# 5V_Regulator.net
KiCad netlist of a schematic drawn in Altium Designer
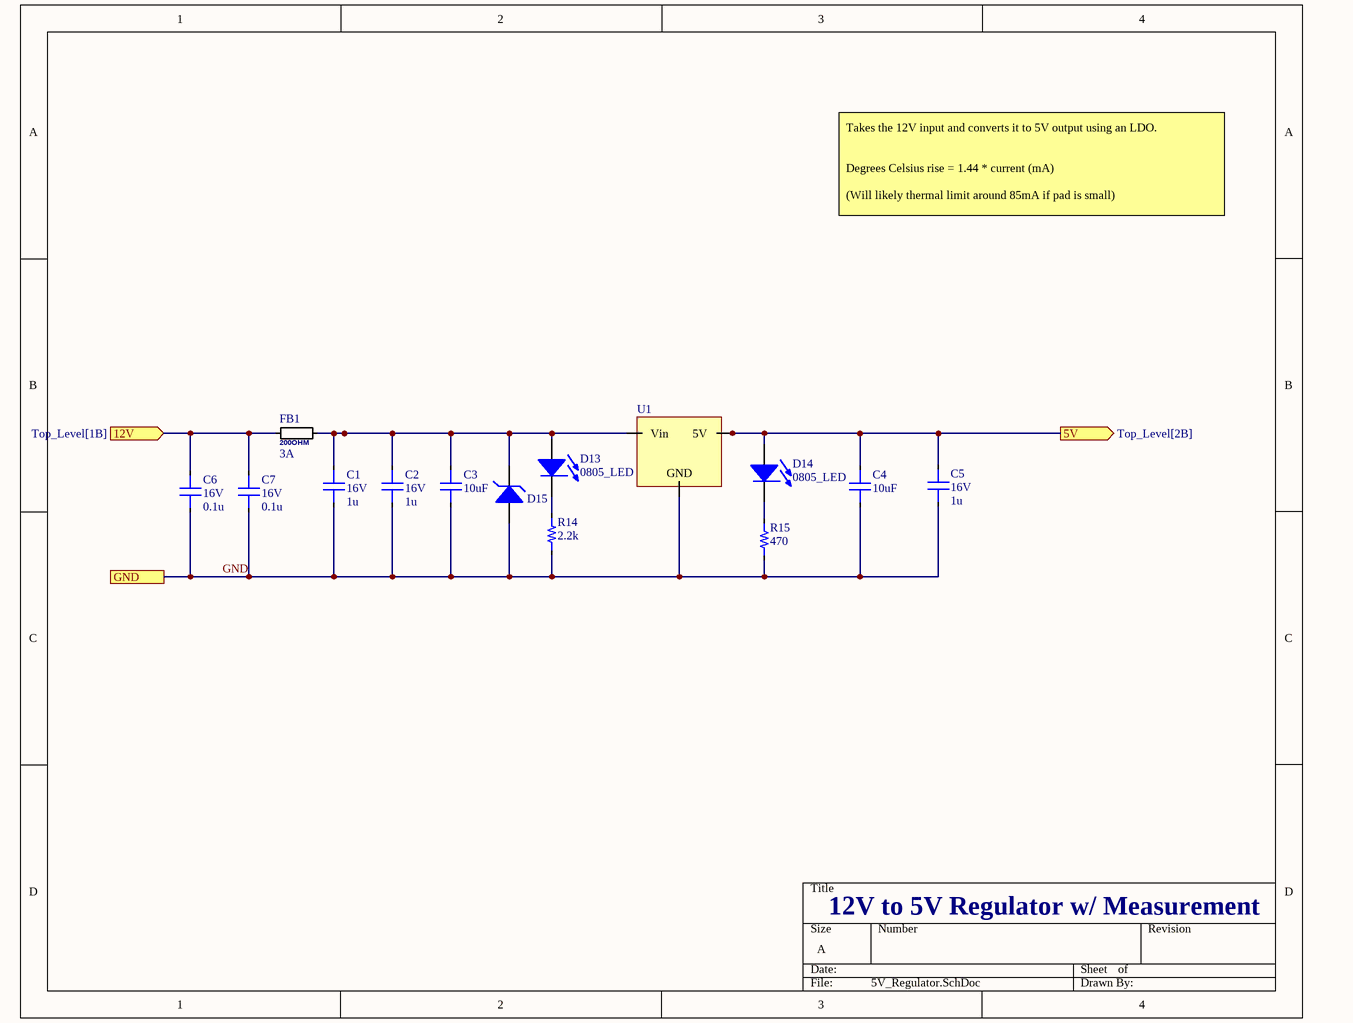
[diagram p0: 5V_Regulator.SchDoc]

(export (version "E")
  (design (tool "Eeschema 10.0.6"))
  (components
    (comp (ref "C1")
      (value "1u")
      (footprint "0603_CAP")
      (fields (field (name "VOLTAGE") "16V") (field (name "Comment") "Capacitor"))
      (libsource (lib "Capacitors") (part "Capacitor"))
    )
    (comp (ref "C2")
      (value "1u")
      (footprint "0603_CAP")
      (fields (field (name "VOLTAGE") "16V") (field (name "Comment") "Capacitor"))
      (libsource (lib "Capacitors") (part "Capacitor"))
    )
    (comp (ref "C3")
      (value "10uF")
      (footprint "0603_CAP")
      (fields (field (name "Comment") "Capacitor"))
      (libsource (lib "Capacitors") (part "Capacitor"))
    )
    (comp (ref "C4")
      (value "10uF")
      (footprint "0603_CAP")
      (fields (field (name "Comment") "Capacitor"))
      (libsource (lib "Capacitors") (part "Capacitor"))
    )
    (comp (ref "C5")
      (value "1u")
      (footprint "0603_CAP")
      (fields (field (name "VOLTAGE") "16V") (field (name "Comment") "Capacitor"))
      (libsource (lib "Capacitors") (part "Capacitor"))
    )
    (comp (ref "C6")
      (value "0.1u")
      (footprint "0603_CAP")
      (fields (field (name "VOLTAGE") "16V") (field (name "Comment") "Capacitor"))
      (libsource (lib "Capacitors") (part "Capacitor"))
    )
    (comp (ref "C7")
      (value "0.1u")
      (footprint "0603_CAP")
      (fields (field (name "VOLTAGE") "16V") (field (name "Comment") "Capacitor"))
      (libsource (lib "Capacitors") (part "Capacitor"))
    )
    (comp (ref "D13")
      (value "0805_LED")
      (footprint "0805_LED")
      (description "Generic 0805 LED")
      (libsource (lib "Diodes") (part "0805_LED"))
    )
    (comp (ref "D14")
      (value "0805_LED")
      (footprint "0805_LED")
      (description "Generic 0805 LED")
      (libsource (lib "Diodes") (part "0805_LED"))
    )
    (comp (ref "D15")
      (value "DDZ9701")
      (footprint "SOD-123")
      (description "Zener Diode 14V 500mW ±5% Surface Mount SOD-1")
      (libsource (lib "Diodes") (part "DDZ9701"))
    )
    (comp (ref "FB1")
      (value "*")
      (footprint "0805_Ferrite")
      (fields (field (name "=Z@100MHZ") "200OHM") (field (name "IMAX") "3A"))
      (libsource (lib "Magnetic") (part "ChipFerrite"))
    )
    (comp (ref "R14")
      (value "2.2k")
      (footprint "0603_RES")
      (fields (field (name "Comment") "Resistor"))
      (libsource (lib "Resistors") (part "Resistor"))
    )
    (comp (ref "R15")
      (value "470")
      (footprint "0603_RES")
      (fields (field (name "Comment") "Resistor"))
      (libsource (lib "Resistors") (part "Resistor"))
    )
    (comp (ref "U1")
      (value "NCP1117ST50T3G")
      (footprint "SOT-233-4")
      (libsource (lib "Power") (part "NCP1117ST50T3G"))
    )
  )
  (nets
    (net (code "1") (name "/5V") (class "Default")
      (node (ref "C4") (pin "2") (pinfunction "2_2") (pintype "passive"))
      (node (ref "C5") (pin "2") (pinfunction "2_2") (pintype "passive"))
      (node (ref "D14") (pin "1") (pinfunction "A_1") (pintype "passive"))
      (node (ref "U1") (pin "2") (pinfunction "5V_2") (pintype "passive"))
      (node (ref "U1") (pin "4") (pinfunction "Tab_4") (pintype "passive"))
    )
    (net (code "2") (name "/12V") (class "Default")
      (node (ref "C6") (pin "2") (pinfunction "2_2") (pintype "passive"))
      (node (ref "C7") (pin "2") (pinfunction "2_2") (pintype "passive"))
      (node (ref "FB1") (pin "1") (pinfunction "1_1") (pintype "passive"))
    )
    (net (code "3") (name "/GND") (class "Default")
      (node (ref "C1") (pin "1") (pinfunction "1_1") (pintype "passive"))
      (node (ref "C2") (pin "1") (pinfunction "1_1") (pintype "passive"))
      (node (ref "C3") (pin "1") (pinfunction "1_1") (pintype "passive"))
      (node (ref "C4") (pin "1") (pinfunction "1_1") (pintype "passive"))
      (node (ref "C5") (pin "1") (pinfunction "1_1") (pintype "passive"))
      (node (ref "C6") (pin "1") (pinfunction "1_1") (pintype "passive"))
      (node (ref "C7") (pin "1") (pinfunction "1_1") (pintype "passive"))
      (node (ref "D15") (pin "2") (pinfunction "A_2") (pintype "passive"))
      (node (ref "R14") (pin "1") (pinfunction "1_1") (pintype "passive"))
      (node (ref "R15") (pin "1") (pinfunction "1_1") (pintype "passive"))
      (node (ref "U1") (pin "1") (pinfunction "GND_1") (pintype "passive"))
    )
    (net (code "4") (name "Net-(D13-A)") (class "Default")
      (node (ref "C1") (pin "2") (pinfunction "2_2") (pintype "passive"))
      (node (ref "C2") (pin "2") (pinfunction "2_2") (pintype "passive"))
      (node (ref "C3") (pin "2") (pinfunction "2_2") (pintype "passive"))
      (node (ref "D13") (pin "1") (pinfunction "A_1") (pintype "passive"))
      (node (ref "D15") (pin "1") (pinfunction "K_1") (pintype "passive"))
      (node (ref "FB1") (pin "2") (pinfunction "2_2") (pintype "passive"))
      (node (ref "U1") (pin "3") (pinfunction "Vin_3") (pintype "passive"))
    )
    (net (code "5") (name "Net-(D13-K)") (class "Default")
      (node (ref "D13") (pin "2") (pinfunction "K_2") (pintype "passive"))
      (node (ref "R14") (pin "2") (pinfunction "2_2") (pintype "passive"))
    )
    (net (code "6") (name "Net-(D14-K)") (class "Default")
      (node (ref "D14") (pin "2") (pinfunction "K_2") (pintype "passive"))
      (node (ref "R15") (pin "2") (pinfunction "2_2") (pintype "passive"))
    )
  )
)
